# IDP.net
KiCad netlist of a schematic drawn in EAGLE
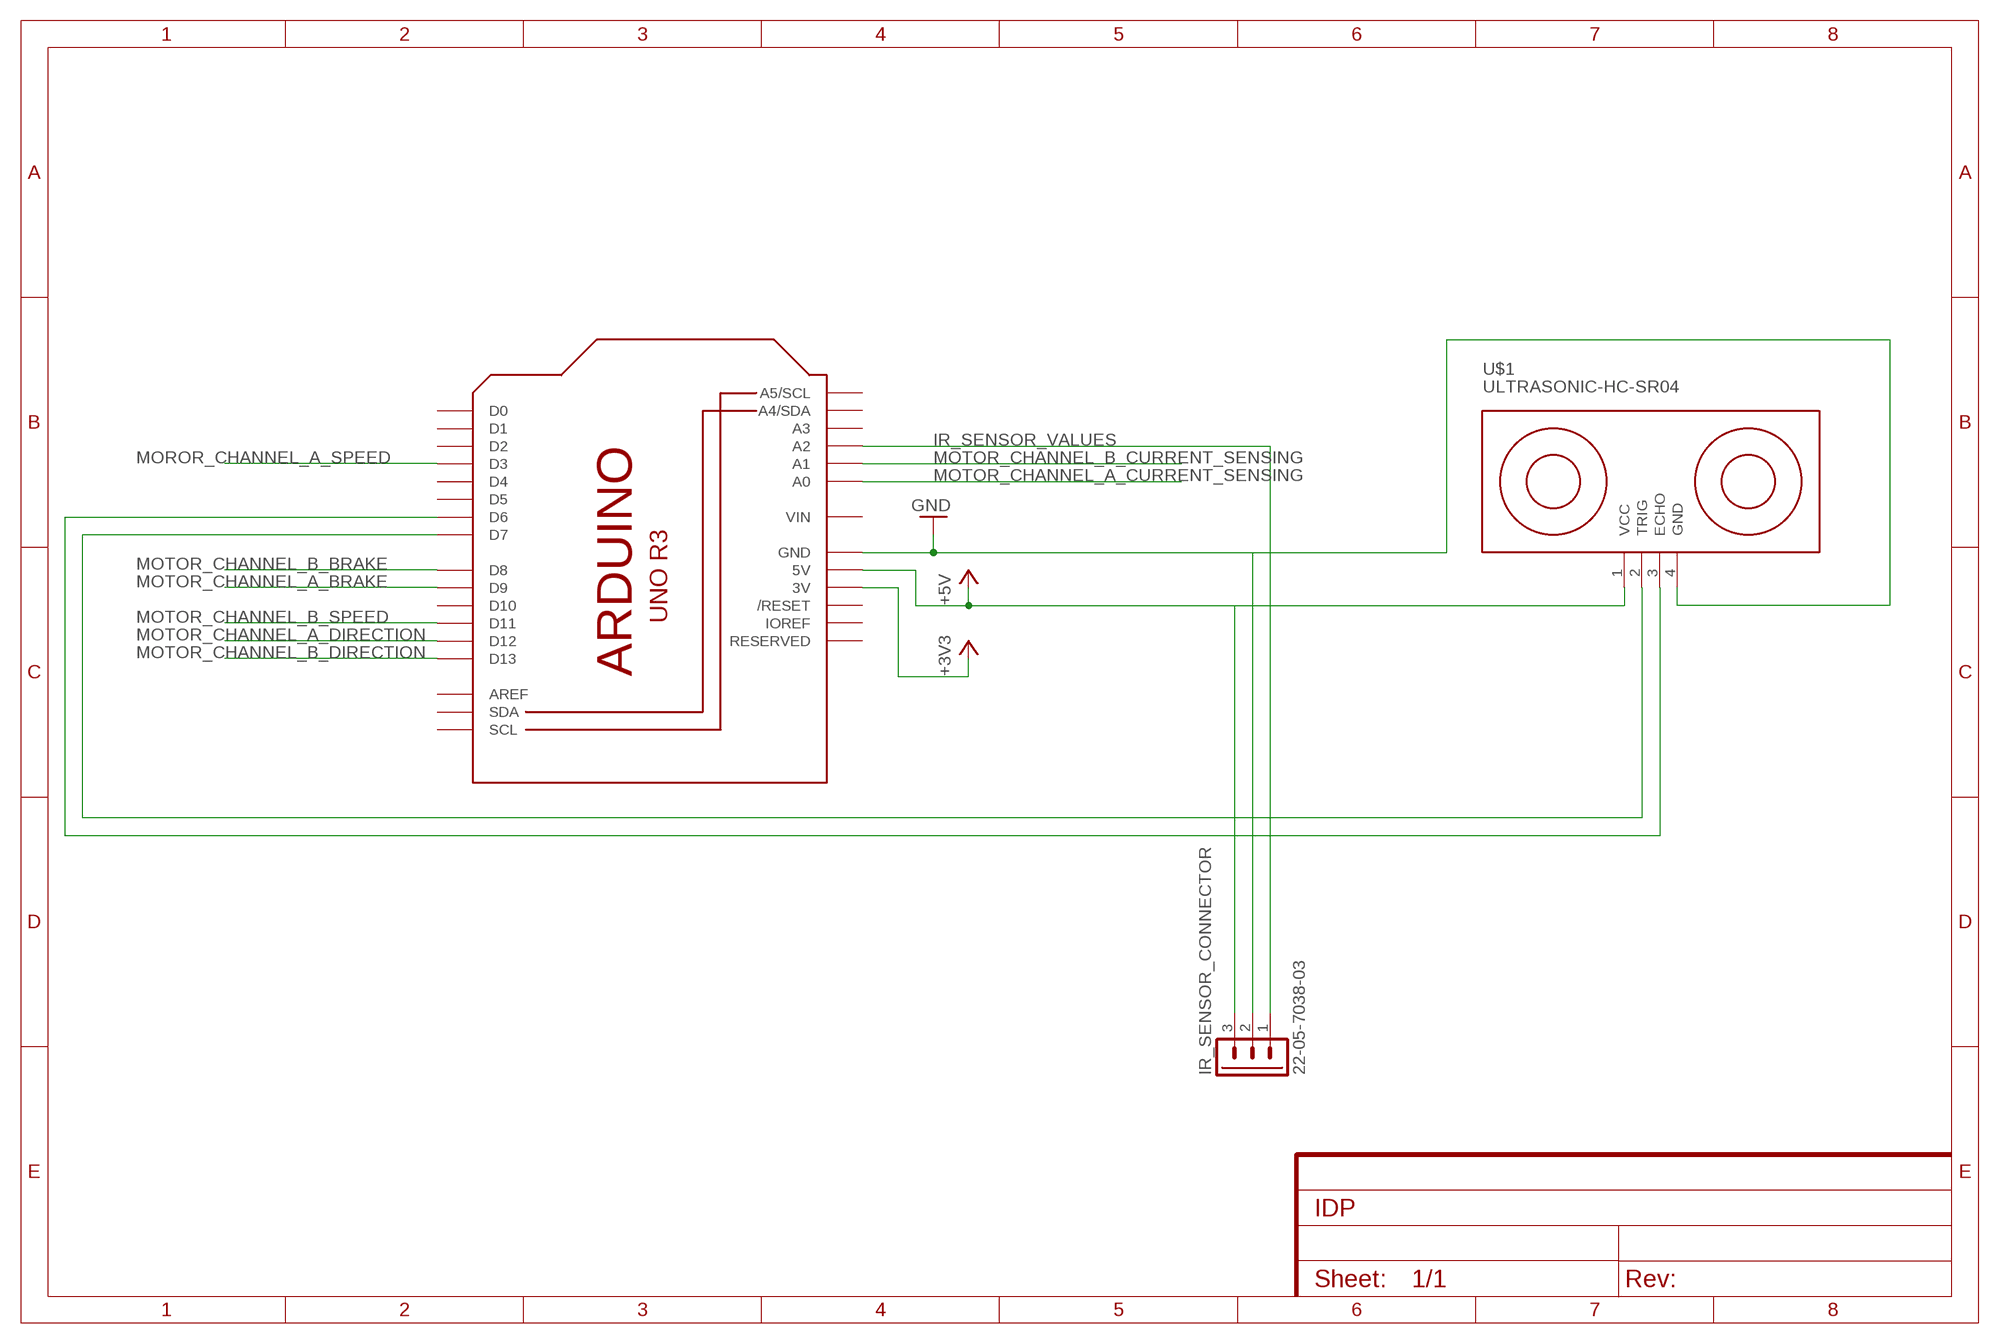
[diagram p0: schematic, sheet 1]

(export (version "E")
  (design (tool "Eeschema 10.0.6"))
  (components
    (comp (ref "IR_SENSOR_CONNECTOR")
      (value "22-05-7038-03")
      (footprint "eagle-import:7395-03")
      (fields (field (name "MF") "MOLEX"))
      (libsource (lib "eagle-import") (part "22-?-0305-7038"))
    )
    (comp (ref "M1")
      (value "IDP_PROTOBOARD")
      (footprint "eagle-import:IDP_PROTO")
      (libsource (lib "eagle-import") (part "IDP_PROTOBOARD"))
    )
    (comp (ref "U$1")
      (value "ULTRASONIC-HC-SR04")
      (footprint "eagle-import:ULTRASONIC-HC-SR04")
      (libsource (lib "eagle-import") (part "ULTRASONIC-HC-SR04"))
    )
  )
  (nets
    (net (code "1") (name "+3V3") (class "Default")
      (node (ref "M1") (pin "3V") (pinfunction "3V_3V") (pintype "power_in"))
    )
    (net (code "2") (name "+5V") (class "Default")
      (node (ref "IR_SENSOR_CONNECTOR") (pin "3") (pinfunction "3_3") (pintype "passive"))
      (node (ref "M1") (pin "5V") (pinfunction "5V_5V") (pintype "power_in"))
      (node (ref "M1") (pin "5V@0") (pinfunction "5V_5V@0") (pintype "power_in"))
      (node (ref "M1") (pin "5V@1") (pinfunction "5V_5V@1") (pintype "power_in"))
      (node (ref "M1") (pin "5V@10") (pinfunction "5V_5V@10") (pintype "power_in"))
      (node (ref "M1") (pin "5V@11") (pinfunction "5V_5V@11") (pintype "power_in"))
      (node (ref "M1") (pin "5V@12") (pinfunction "5V_5V@12") (pintype "power_in"))
      (node (ref "M1") (pin "5V@13") (pinfunction "5V_5V@13") (pintype "power_in"))
      (node (ref "M1") (pin "5V@14") (pinfunction "5V_5V@14") (pintype "power_in"))
      (node (ref "M1") (pin "5V@15") (pinfunction "5V_5V@15") (pintype "power_in"))
      (node (ref "M1") (pin "5V@16") (pinfunction "5V_5V@16") (pintype "power_in"))
      (node (ref "M1") (pin "5V@17") (pinfunction "5V_5V@17") (pintype "power_in"))
      (node (ref "M1") (pin "5V@18") (pinfunction "5V_5V@18") (pintype "power_in"))
      (node (ref "M1") (pin "5V@19") (pinfunction "5V_5V@19") (pintype "power_in"))
      (node (ref "M1") (pin "5V@2") (pinfunction "5V_5V@2") (pintype "power_in"))
      (node (ref "M1") (pin "5V@20") (pinfunction "5V_5V@20") (pintype "power_in"))
      (node (ref "M1") (pin "5V@21") (pinfunction "5V_5V@21") (pintype "power_in"))
      (node (ref "M1") (pin "5V@22") (pinfunction "5V_5V@22") (pintype "power_in"))
      (node (ref "M1") (pin "5V@23") (pinfunction "5V_5V@23") (pintype "power_in"))
      (node (ref "M1") (pin "5V@24") (pinfunction "5V_5V@24") (pintype "power_in"))
      (node (ref "M1") (pin "5V@25") (pinfunction "5V_5V@25") (pintype "power_in"))
      (node (ref "M1") (pin "5V@26") (pinfunction "5V_5V@26") (pintype "power_in"))
      (node (ref "M1") (pin "5V@27") (pinfunction "5V_5V@27") (pintype "power_in"))
      (node (ref "M1") (pin "5V@28") (pinfunction "5V_5V@28") (pintype "power_in"))
      (node (ref "M1") (pin "5V@29") (pinfunction "5V_5V@29") (pintype "power_in"))
      (node (ref "M1") (pin "5V@3") (pinfunction "5V_5V@3") (pintype "power_in"))
      (node (ref "M1") (pin "5V@30") (pinfunction "5V_5V@30") (pintype "power_in"))
      (node (ref "M1") (pin "5V@31") (pinfunction "5V_5V@31") (pintype "power_in"))
      (node (ref "M1") (pin "5V@32") (pinfunction "5V_5V@32") (pintype "power_in"))
      (node (ref "M1") (pin "5V@33") (pinfunction "5V_5V@33") (pintype "power_in"))
      (node (ref "M1") (pin "5V@34") (pinfunction "5V_5V@34") (pintype "power_in"))
      (node (ref "M1") (pin "5V@35") (pinfunction "5V_5V@35") (pintype "power_in"))
      (node (ref "M1") (pin "5V@36") (pinfunction "5V_5V@36") (pintype "power_in"))
      (node (ref "M1") (pin "5V@37") (pinfunction "5V_5V@37") (pintype "power_in"))
      (node (ref "M1") (pin "5V@38") (pinfunction "5V_5V@38") (pintype "power_in"))
      (node (ref "M1") (pin "5V@39") (pinfunction "5V_5V@39") (pintype "power_in"))
      (node (ref "M1") (pin "5V@4") (pinfunction "5V_5V@4") (pintype "power_in"))
      (node (ref "M1") (pin "5V@40") (pinfunction "5V_5V@40") (pintype "power_in"))
      (node (ref "M1") (pin "5V@5") (pinfunction "5V_5V@5") (pintype "power_in"))
      (node (ref "M1") (pin "5V@6") (pinfunction "5V_5V@6") (pintype "power_in"))
      (node (ref "M1") (pin "5V@7") (pinfunction "5V_5V@7") (pintype "power_in"))
      (node (ref "M1") (pin "5V@8") (pinfunction "5V_5V@8") (pintype "power_in"))
      (node (ref "M1") (pin "5V@9") (pinfunction "5V_5V@9") (pintype "power_in"))
      (node (ref "U$1") (pin "1") (pinfunction "VCC_1") (pintype "power_in"))
    )
    (net (code "3") (name "/IR_SENSOR_VALUES") (class "Default")
      (node (ref "IR_SENSOR_CONNECTOR") (pin "1") (pinfunction "1_1") (pintype "passive"))
      (node (ref "M1") (pin "A2") (pinfunction "A2_A2") (pintype "bidirectional"))
    )
    (net (code "4") (name "/MOROR_CHANNEL_A_SPEED") (class "Default")
      (node (ref "M1") (pin "D3") (pinfunction "D3_D3") (pintype "bidirectional"))
    )
    (net (code "5") (name "/MOTOR_CHANNEL_A_BRAKE") (class "Default")
      (node (ref "M1") (pin "D9") (pinfunction "D9_D9") (pintype "bidirectional"))
    )
    (net (code "6") (name "/MOTOR_CHANNEL_A_CURRENT_SENSING") (class "Default")
      (node (ref "M1") (pin "A0") (pinfunction "A0_A0") (pintype "bidirectional"))
    )
    (net (code "7") (name "/MOTOR_CHANNEL_A_DIRECTION") (class "Default")
      (node (ref "M1") (pin "D12") (pinfunction "D12_D12") (pintype "bidirectional"))
    )
    (net (code "8") (name "/MOTOR_CHANNEL_B_BRAKE") (class "Default")
      (node (ref "M1") (pin "D8") (pinfunction "D8_D8") (pintype "bidirectional"))
    )
    (net (code "9") (name "/MOTOR_CHANNEL_B_CURRENT_SENSING") (class "Default")
      (node (ref "M1") (pin "A1") (pinfunction "A1_A1") (pintype "bidirectional"))
    )
    (net (code "10") (name "/MOTOR_CHANNEL_B_DIRECTION") (class "Default")
      (node (ref "M1") (pin "D13") (pinfunction "D13_D13") (pintype "bidirectional"))
    )
    (net (code "11") (name "/MOTOR_CHANNEL_B_SPEED") (class "Default")
      (node (ref "M1") (pin "D11") (pinfunction "D11_D11") (pintype "bidirectional"))
    )
    (net (code "12") (name "GND") (class "Default")
      (node (ref "IR_SENSOR_CONNECTOR") (pin "2") (pinfunction "2_2") (pintype "passive"))
      (node (ref "M1") (pin "GND") (pinfunction "GND_GND") (pintype "power_in"))
      (node (ref "M1") (pin "GND16") (pinfunction "GND_GND16") (pintype "power_in"))
      (node (ref "M1") (pin "GND17") (pinfunction "GND_GND17") (pintype "power_in"))
      (node (ref "M1") (pin "GND18") (pinfunction "GND_GND18") (pintype "power_in"))
      (node (ref "M1") (pin "GND19") (pinfunction "GND_GND19") (pintype "power_in"))
      (node (ref "M1") (pin "GND20") (pinfunction "GND_GND20") (pintype "power_in"))
      (node (ref "M1") (pin "GND21") (pinfunction "GND_GND21") (pintype "power_in"))
      (node (ref "M1") (pin "GND22") (pinfunction "GND_GND22") (pintype "power_in"))
      (node (ref "M1") (pin "GND23") (pinfunction "GND_GND23") (pintype "power_in"))
      (node (ref "M1") (pin "GND24") (pinfunction "GND_GND24") (pintype "power_in"))
      (node (ref "M1") (pin "GND25") (pinfunction "GND_GND25") (pintype "power_in"))
      (node (ref "M1") (pin "GND@1") (pinfunction "GND_GND@1") (pintype "power_in"))
      (node (ref "M1") (pin "GND@10") (pinfunction "GND_GND@10") (pintype "power_in"))
      (node (ref "M1") (pin "GND@11") (pinfunction "GND_GND@11") (pintype "power_in"))
      (node (ref "M1") (pin "GND@12") (pinfunction "GND_GND@12") (pintype "power_in"))
      (node (ref "M1") (pin "GND@13") (pinfunction "GND_GND@13") (pintype "power_in"))
      (node (ref "M1") (pin "GND@14") (pinfunction "GND_GND@14") (pintype "power_in"))
      (node (ref "M1") (pin "GND@15") (pinfunction "GND_GND@15") (pintype "power_in"))
      (node (ref "M1") (pin "GND@2") (pinfunction "GND_GND@2") (pintype "power_in"))
      (node (ref "M1") (pin "GND@26") (pinfunction "GND_GND@26") (pintype "power_in"))
      (node (ref "M1") (pin "GND@27") (pinfunction "GND_GND@27") (pintype "power_in"))
      (node (ref "M1") (pin "GND@28") (pinfunction "GND_GND@28") (pintype "power_in"))
      (node (ref "M1") (pin "GND@29") (pinfunction "GND_GND@29") (pintype "power_in"))
      (node (ref "M1") (pin "GND@3") (pinfunction "GND_GND@3") (pintype "power_in"))
      (node (ref "M1") (pin "GND@30") (pinfunction "GND_GND@30") (pintype "power_in"))
      (node (ref "M1") (pin "GND@31") (pinfunction "GND_GND@31") (pintype "power_in"))
      (node (ref "M1") (pin "GND@32") (pinfunction "GND_GND@32") (pintype "power_in"))
      (node (ref "M1") (pin "GND@33") (pinfunction "GND_GND@33") (pintype "power_in"))
      (node (ref "M1") (pin "GND@34") (pinfunction "GND_GND@34") (pintype "power_in"))
      (node (ref "M1") (pin "GND@35") (pinfunction "GND_GND@35") (pintype "power_in"))
      (node (ref "M1") (pin "GND@36") (pinfunction "GND_GND@36") (pintype "power_in"))
      (node (ref "M1") (pin "GND@37") (pinfunction "GND_GND@37") (pintype "power_in"))
      (node (ref "M1") (pin "GND@38") (pinfunction "GND_GND@38") (pintype "power_in"))
      (node (ref "M1") (pin "GND@39") (pinfunction "GND_GND@39") (pintype "power_in"))
      (node (ref "M1") (pin "GND@4") (pinfunction "GND_GND@4") (pintype "power_in"))
      (node (ref "M1") (pin "GND@40") (pinfunction "GND_GND@40") (pintype "power_in"))
      (node (ref "M1") (pin "GND@41") (pinfunction "GND_GND@41") (pintype "power_in"))
      (node (ref "M1") (pin "GND@42") (pinfunction "GND_GND@42") (pintype "power_in"))
      (node (ref "M1") (pin "GND@43") (pinfunction "GND_GND@43") (pintype "power_in"))
      (node (ref "M1") (pin "GND@44") (pinfunction "GND_GND@44") (pintype "power_in"))
      (node (ref "M1") (pin "GND@45") (pinfunction "GND_GND@45") (pintype "power_in"))
      (node (ref "M1") (pin "GND@46") (pinfunction "GND_GND@46") (pintype "power_in"))
      (node (ref "M1") (pin "GND@47") (pinfunction "GND_GND@47") (pintype "power_in"))
      (node (ref "M1") (pin "GND@48") (pinfunction "GND_GND@48") (pintype "power_in"))
      (node (ref "M1") (pin "GND@5") (pinfunction "GND_GND@5") (pintype "power_in"))
      (node (ref "M1") (pin "GND@6") (pinfunction "GND_GND@6") (pintype "power_in"))
      (node (ref "M1") (pin "GND@7") (pinfunction "GND_GND@7") (pintype "power_in"))
      (node (ref "M1") (pin "GND@8") (pinfunction "GND_GND@8") (pintype "power_in"))
      (node (ref "M1") (pin "GND@9") (pinfunction "GND_GND@9") (pintype "power_in"))
      (node (ref "U$1") (pin "4") (pinfunction "GND_4") (pintype "power_in"))
    )
    (net (code "13") (name "Net-(U$1-ECHO)") (class "Default")
      (node (ref "M1") (pin "D6") (pinfunction "D6_D6") (pintype "bidirectional"))
      (node (ref "U$1") (pin "3") (pinfunction "ECHO_3") (pintype "output"))
    )
    (net (code "14") (name "Net-(U$1-TRIG)") (class "Default")
      (node (ref "M1") (pin "D7") (pinfunction "D7_D7") (pintype "bidirectional"))
      (node (ref "U$1") (pin "2") (pinfunction "TRIG_2") (pintype "input"))
    )
    (net (code "15") (name "unconnected-(M1-A4{slash}SDA-PadA4)") (class "Default")
      (node (ref "M1") (pin "A4") (pinfunction "A4/SDA_A4") (pintype "bidirectional"))
    )
    (net (code "16") (name "unconnected-(M1-A5{slash}SCL-PadA5)") (class "Default")
      (node (ref "M1") (pin "A5") (pinfunction "A5/SCL_A5") (pintype "bidirectional"))
    )
    (net (code "17") (name "unconnected-(M1-PadA3)") (class "Default")
      (node (ref "M1") (pin "A3") (pinfunction "A3_A3") (pintype "bidirectional"))
    )
    (net (code "18") (name "unconnected-(M1-PadAREF)") (class "Default")
      (node (ref "M1") (pin "AREF") (pinfunction "AREF_AREF") (pintype "bidirectional"))
    )
    (net (code "19") (name "unconnected-(M1-PadD0)") (class "Default")
      (node (ref "M1") (pin "D0") (pinfunction "D0_D0") (pintype "bidirectional"))
    )
    (net (code "20") (name "unconnected-(M1-PadD1)") (class "Default")
      (node (ref "M1") (pin "D1") (pinfunction "D1_D1") (pintype "bidirectional"))
    )
    (net (code "21") (name "unconnected-(M1-PadD2)") (class "Default")
      (node (ref "M1") (pin "D2") (pinfunction "D2_D2") (pintype "bidirectional"))
    )
    (net (code "22") (name "unconnected-(M1-PadD4)") (class "Default")
      (node (ref "M1") (pin "D4") (pinfunction "D4_D4") (pintype "bidirectional"))
    )
    (net (code "23") (name "unconnected-(M1-PadD5)") (class "Default")
      (node (ref "M1") (pin "D5") (pinfunction "D5_D5") (pintype "bidirectional"))
    )
    (net (code "24") (name "unconnected-(M1-PadD10)") (class "Default")
      (node (ref "M1") (pin "D10") (pinfunction "D10_D10") (pintype "bidirectional"))
    )
    (net (code "25") (name "unconnected-(M1-PadIOREF)") (class "Default")
      (node (ref "M1") (pin "IOREF") (pinfunction "IOREF_IOREF") (pintype "output"))
    )
    (net (code "26") (name "unconnected-(M1-PadRESERVED)") (class "Default")
      (node (ref "M1") (pin "RESERVED") (pinfunction "RESERVED_RESERVED") (pintype "no_connect"))
    )
    (net (code "27") (name "unconnected-(M1-PadSCL)") (class "Default")
      (node (ref "M1") (pin "SCL") (pinfunction "SCL_SCL") (pintype "bidirectional"))
    )
    (net (code "28") (name "unconnected-(M1-PadSDA)") (class "Default")
      (node (ref "M1") (pin "SDA") (pinfunction "SDA_SDA") (pintype "bidirectional"))
    )
    (net (code "29") (name "unconnected-(M1-PadVIN)") (class "Default")
      (node (ref "M1") (pin "VIN") (pinfunction "VIN_VIN") (pintype "no_connect"))
    )
    (net (code "30") (name "unconnected-(M1-{slash}RESET-PadRESET)") (class "Default")
      (node (ref "M1") (pin "RESET") (pinfunction "/RESET_RESET") (pintype "bidirectional"))
    )
  )
)
